# Lasers.net
KiCad netlist of a schematic drawn in Altium Designer
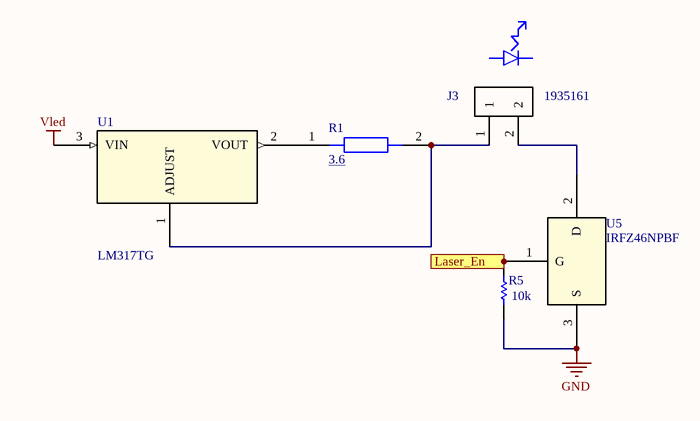
[diagram p0: Lasers.SchDoc]

(export (version "E")
  (design (tool "Eeschema 10.0.6"))
  (components
    (comp (ref "J3")
      (value "1935161")
      (footprint "PHOENIX_1935161")
      (description "Conn Terminal Blocks 2 POS 5mm Solder ST Thru-Hole 16A")
      (fields (field (name "DIGI-KEY_PART_NUMBER") "277-1667-ND") (field (name "MF") "Phoenix Contact"))
      (libsource (lib "Laser") (part "1935161"))
    )
    (comp (ref "R1") (value "3.6") (footprint "3.6_R") (libsource (lib "Laser") (part "3.6")))
    (comp (ref "R5")
      (value "10k")
      (footprint "AXIAL-0.3")
      (description "Resistor")
      (fields (field (name "Comment") "Res1") (field (name "PUBLISHER") "Altium Limited"))
      (libsource (lib "Miscellaneous Devices") (part "Res1"))
    )
    (comp (ref "U1")
      (value "LM317TG")
      (footprint "TO-220AB")
      (description "Imported")
      (libsource (lib "Laser") (part "LM317TG"))
    )
    (comp (ref "U5")
      (value "IRFZ46NPBF")
      (footprint "TO-220AB")
      (description "Imported")
      (libsource (lib "Laser") (part "IRFZ46NPBF"))
    )
  )
  (nets
    (net (code "1") (name "/Laser_En") (class "Default")
      (node (ref "R5") (pin "2") (pinfunction "2_2") (pintype "passive"))
      (node (ref "U5") (pin "1") (pinfunction "G_1") (pintype "passive"))
    )
    (net (code "2") (name "GND") (class "Default")
      (node (ref "R5") (pin "1") (pinfunction "1_1") (pintype "passive"))
      (node (ref "U5") (pin "3") (pinfunction "S_3") (pintype "passive"))
    )
    (net (code "3") (name "Net-(U1-ADJUST)") (class "Default")
      (node (ref "J3") (pin "1") (pinfunction "1_1") (pintype "passive"))
      (node (ref "R1") (pin "2") (pinfunction "2_2") (pintype "passive"))
      (node (ref "U1") (pin "1") (pinfunction "ADJUST_1") (pintype "passive"))
    )
    (net (code "4") (name "Net-(U1-VOUT)") (class "Default")
      (node (ref "R1") (pin "1") (pinfunction "1_1") (pintype "passive"))
      (node (ref "U1") (pin "2") (pinfunction "VOUT_2") (pintype "output"))
    )
    (net (code "5") (name "Net-(U5-D)") (class "Default")
      (node (ref "J3") (pin "2") (pinfunction "2_2") (pintype "passive"))
      (node (ref "U5") (pin "2") (pinfunction "D_2") (pintype "passive"))
    )
    (net (code "6") (name "Vled") (class "Default")
      (node (ref "U1") (pin "3") (pinfunction "VIN_3") (pintype "input"))
    )
  )
)
